# Clock.net
KiCad netlist of a schematic drawn in EAGLE
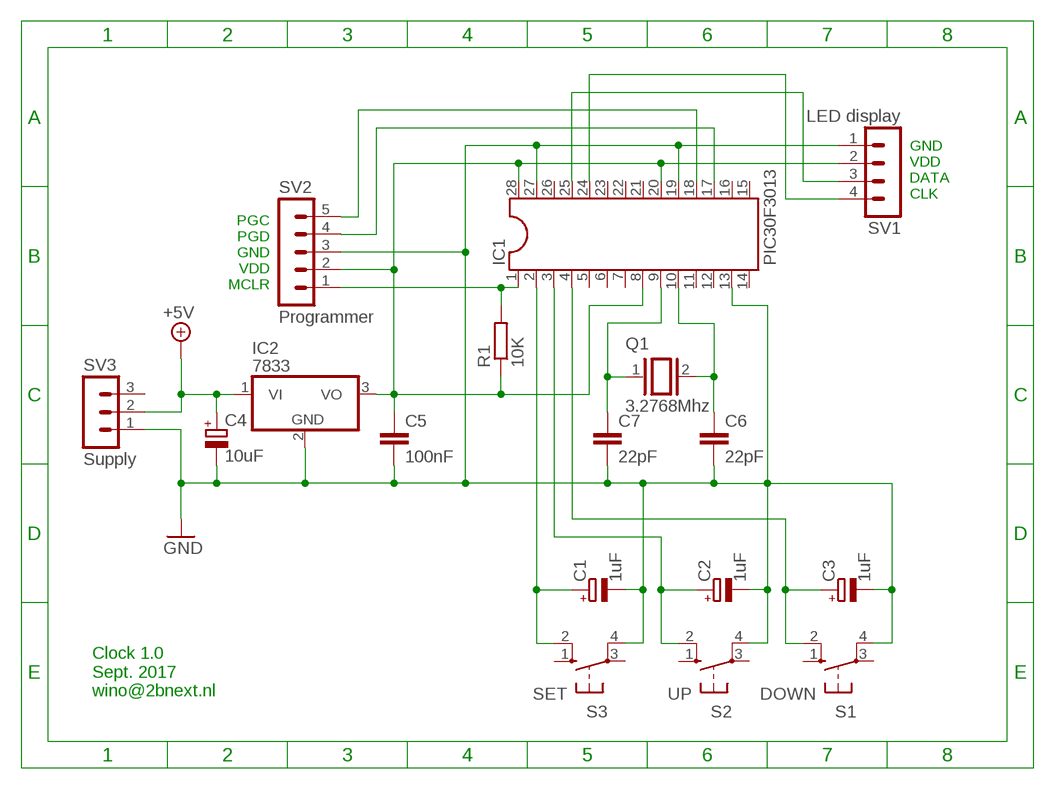
[diagram p0: schematic, sheet 1]

(export (version "E")
  (design (tool "Eeschema 10.0.6"))
  (components
    (comp (ref "C1")
      (value "1uF")
      (footprint "eagle-import:E2,5-5")
      (libsource (lib "eagle-import") (part "CPOL-EUE2.5-5"))
    )
    (comp (ref "C2")
      (value "1uF")
      (footprint "eagle-import:E2,5-5")
      (libsource (lib "eagle-import") (part "CPOL-EUE2.5-5"))
    )
    (comp (ref "C3")
      (value "1uF")
      (footprint "eagle-import:E2,5-5")
      (libsource (lib "eagle-import") (part "CPOL-EUE2.5-5"))
    )
    (comp (ref "C4")
      (value "10uF")
      (footprint "eagle-import:E2,5-5")
      (libsource (lib "eagle-import") (part "CPOL-EUE2.5-5"))
    )
    (comp (ref "C5")
      (value "100nF")
      (footprint "eagle-import:C2.5-3")
      (libsource (lib "eagle-import") (part "C2,5-3"))
    )
    (comp (ref "C6")
      (value "22pF")
      (footprint "eagle-import:C2.5-3")
      (libsource (lib "eagle-import") (part "C2,5-3"))
    )
    (comp (ref "C7")
      (value "22pF")
      (footprint "eagle-import:C2.5-3")
      (libsource (lib "eagle-import") (part "C2,5-3"))
    )
    (comp (ref "IC1")
      (value "PIC30F3013")
      (footprint "eagle-import:DIL28-3")
      (libsource (lib "eagle-import") (part "DIL28-3"))
    )
    (comp (ref "IC2")
      (value "7833")
      (footprint "eagle-import:TO220H")
      (libsource (lib "eagle-import") (part "78T05"))
    )
    (comp (ref "Q1")
      (value "3.2768Mhz")
      (footprint "eagle-import:QS")
      (libsource (lib "eagle-import") (part "XTAL/S"))
    )
    (comp (ref "R1")
      (value "10K")
      (footprint "eagle-import:0207_7")
      (libsource (lib "eagle-import") (part "R-EU_0207/7"))
    )
    (comp (ref "S1")
      (value "DOWN")
      (footprint "eagle-import:B3F-10XX")
      (fields (field (name "MPN") "B3F-1000"))
      (libsource (lib "eagle-import") (part "10-XX"))
    )
    (comp (ref "S2")
      (value "UP")
      (footprint "eagle-import:B3F-10XX")
      (fields (field (name "MPN") "B3F-1000"))
      (libsource (lib "eagle-import") (part "10-XX"))
    )
    (comp (ref "S3")
      (value "SET")
      (footprint "eagle-import:B3F-10XX")
      (fields (field (name "MPN") "B3F-1000"))
      (libsource (lib "eagle-import") (part "10-XX"))
    )
    (comp (ref "SV1")
      (value "LED display")
      (footprint "eagle-import:MA04-1")
      (libsource (lib "eagle-import") (part "MA04-1"))
    )
    (comp (ref "SV2")
      (value "Programmer")
      (footprint "eagle-import:MA05-1")
      (libsource (lib "eagle-import") (part "MA05-1"))
    )
    (comp (ref "SV3")
      (value "Supply")
      (footprint "eagle-import:MA03-1")
      (libsource (lib "eagle-import") (part "MA03-1"))
    )
  )
  (nets
    (net (code "1") (name "+5V") (class "Default")
      (node (ref "C4") (pin "+") (pinfunction "+_+") (pintype "passive"))
      (node (ref "IC2") (pin "1") (pinfunction "VI_1") (pintype "input"))
      (node (ref "SV3") (pin "2") (pinfunction "2_2") (pintype "passive"))
    )
    (net (code "2") (name "GND") (class "Default")
      (node (ref "C1") (pin "-") (pinfunction "-_-") (pintype "passive"))
      (node (ref "C2") (pin "-") (pinfunction "-_-") (pintype "passive"))
      (node (ref "C3") (pin "-") (pinfunction "-_-") (pintype "passive"))
      (node (ref "C4") (pin "-") (pinfunction "-_-") (pintype "passive"))
      (node (ref "C5") (pin "2") (pinfunction "2_2") (pintype "passive"))
      (node (ref "C6") (pin "2") (pinfunction "2_2") (pintype "passive"))
      (node (ref "C7") (pin "2") (pinfunction "2_2") (pintype "passive"))
      (node (ref "IC1") (pin "13") (pinfunction "13_13") (pintype "passive"))
      (node (ref "IC1") (pin "19") (pinfunction "19_19") (pintype "passive"))
      (node (ref "IC1") (pin "27") (pinfunction "27_27") (pintype "passive"))
      (node (ref "IC2") (pin "2") (pinfunction "GND_2") (pintype "passive"))
      (node (ref "S1") (pin "4") (pinfunction "P1_4") (pintype "passive"))
      (node (ref "S2") (pin "4") (pinfunction "P1_4") (pintype "passive"))
      (node (ref "S3") (pin "4") (pinfunction "P1_4") (pintype "passive"))
      (node (ref "SV1") (pin "1") (pinfunction "1_1") (pintype "passive"))
      (node (ref "SV2") (pin "3") (pinfunction "3_3") (pintype "passive"))
      (node (ref "SV3") (pin "1") (pinfunction "1_1") (pintype "passive"))
    )
    (net (code "3") (name "Net-(C6-Pad1)") (class "Default")
      (node (ref "C6") (pin "1") (pinfunction "1_1") (pintype "passive"))
      (node (ref "IC1") (pin "10") (pinfunction "10_10") (pintype "passive"))
      (node (ref "Q1") (pin "2") (pinfunction "2_2") (pintype "passive"))
    )
    (net (code "4") (name "Net-(C7-Pad1)") (class "Default")
      (node (ref "C7") (pin "1") (pinfunction "1_1") (pintype "passive"))
      (node (ref "IC1") (pin "9") (pinfunction "9_9") (pintype "passive"))
      (node (ref "Q1") (pin "1") (pinfunction "1_1") (pintype "passive"))
    )
    (net (code "5") (name "Net-(IC1-Pad1)") (class "Default")
      (node (ref "IC1") (pin "1") (pinfunction "1_1") (pintype "passive"))
      (node (ref "R1") (pin "2") (pinfunction "2_2") (pintype "passive"))
      (node (ref "SV2") (pin "1") (pinfunction "1_1") (pintype "passive"))
    )
    (net (code "6") (name "Net-(IC1-Pad17)") (class "Default")
      (node (ref "IC1") (pin "17") (pinfunction "17_17") (pintype "passive"))
      (node (ref "SV2") (pin "4") (pinfunction "4_4") (pintype "passive"))
    )
    (net (code "7") (name "Net-(IC1-Pad18)") (class "Default")
      (node (ref "IC1") (pin "18") (pinfunction "18_18") (pintype "passive"))
      (node (ref "SV2") (pin "5") (pinfunction "5_5") (pintype "passive"))
    )
    (net (code "8") (name "Net-(IC1-Pad24)") (class "Default")
      (node (ref "IC1") (pin "24") (pinfunction "24_24") (pintype "passive"))
      (node (ref "SV1") (pin "4") (pinfunction "4_4") (pintype "passive"))
    )
    (net (code "9") (name "Net-(IC1-Pad25)") (class "Default")
      (node (ref "IC1") (pin "25") (pinfunction "25_25") (pintype "passive"))
      (node (ref "SV1") (pin "3") (pinfunction "3_3") (pintype "passive"))
    )
    (net (code "10") (name "Net-(IC2-VO)") (class "Default")
      (node (ref "C5") (pin "1") (pinfunction "1_1") (pintype "passive"))
      (node (ref "IC1") (pin "20") (pinfunction "20_20") (pintype "passive"))
      (node (ref "IC1") (pin "28") (pinfunction "28_28") (pintype "passive"))
      (node (ref "IC1") (pin "8") (pinfunction "8_8") (pintype "passive"))
      (node (ref "IC2") (pin "3") (pinfunction "VO_3") (pintype "passive"))
      (node (ref "R1") (pin "1") (pinfunction "1_1") (pintype "passive"))
      (node (ref "SV1") (pin "2") (pinfunction "2_2") (pintype "passive"))
      (node (ref "SV2") (pin "2") (pinfunction "2_2") (pintype "passive"))
    )
    (net (code "11") (name "Net-(S1-S1)") (class "Default")
      (node (ref "C3") (pin "+") (pinfunction "+_+") (pintype "passive"))
      (node (ref "IC1") (pin "4") (pinfunction "4_4") (pintype "passive"))
      (node (ref "S1") (pin "2") (pinfunction "S1_2") (pintype "passive"))
    )
    (net (code "12") (name "Net-(S2-S1)") (class "Default")
      (node (ref "C2") (pin "+") (pinfunction "+_+") (pintype "passive"))
      (node (ref "IC1") (pin "3") (pinfunction "3_3") (pintype "passive"))
      (node (ref "S2") (pin "2") (pinfunction "S1_2") (pintype "passive"))
    )
    (net (code "13") (name "Net-(S3-S1)") (class "Default")
      (node (ref "C1") (pin "+") (pinfunction "+_+") (pintype "passive"))
      (node (ref "IC1") (pin "2") (pinfunction "2_2") (pintype "passive"))
      (node (ref "S3") (pin "2") (pinfunction "S1_2") (pintype "passive"))
    )
    (net (code "14") (name "unconnected-(IC1-Pad5)") (class "Default")
      (node (ref "IC1") (pin "5") (pinfunction "5_5") (pintype "passive"))
    )
    (net (code "15") (name "unconnected-(IC1-Pad6)") (class "Default")
      (node (ref "IC1") (pin "6") (pinfunction "6_6") (pintype "passive"))
    )
    (net (code "16") (name "unconnected-(IC1-Pad7)") (class "Default")
      (node (ref "IC1") (pin "7") (pinfunction "7_7") (pintype "passive"))
    )
    (net (code "17") (name "unconnected-(IC1-Pad11)") (class "Default")
      (node (ref "IC1") (pin "11") (pinfunction "11_11") (pintype "passive"))
    )
    (net (code "18") (name "unconnected-(IC1-Pad12)") (class "Default")
      (node (ref "IC1") (pin "12") (pinfunction "12_12") (pintype "passive"))
    )
    (net (code "19") (name "unconnected-(IC1-Pad14)") (class "Default")
      (node (ref "IC1") (pin "14") (pinfunction "14_14") (pintype "passive"))
    )
    (net (code "20") (name "unconnected-(IC1-Pad15)") (class "Default")
      (node (ref "IC1") (pin "15") (pinfunction "15_15") (pintype "passive"))
    )
    (net (code "21") (name "unconnected-(IC1-Pad16)") (class "Default")
      (node (ref "IC1") (pin "16") (pinfunction "16_16") (pintype "passive"))
    )
    (net (code "22") (name "unconnected-(IC1-Pad21)") (class "Default")
      (node (ref "IC1") (pin "21") (pinfunction "21_21") (pintype "passive"))
    )
    (net (code "23") (name "unconnected-(IC1-Pad22)") (class "Default")
      (node (ref "IC1") (pin "22") (pinfunction "22_22") (pintype "passive"))
    )
    (net (code "24") (name "unconnected-(IC1-Pad23)") (class "Default")
      (node (ref "IC1") (pin "23") (pinfunction "23_23") (pintype "passive"))
    )
    (net (code "25") (name "unconnected-(IC1-Pad26)") (class "Default")
      (node (ref "IC1") (pin "26") (pinfunction "26_26") (pintype "passive"))
    )
    (net (code "26") (name "unconnected-(S1-P-Pad3)") (class "Default")
      (node (ref "S1") (pin "3") (pinfunction "P_3") (pintype "passive"))
    )
    (net (code "27") (name "unconnected-(S1-S-Pad1)") (class "Default")
      (node (ref "S1") (pin "1") (pinfunction "S_1") (pintype "passive"))
    )
    (net (code "28") (name "unconnected-(S2-P-Pad3)") (class "Default")
      (node (ref "S2") (pin "3") (pinfunction "P_3") (pintype "passive"))
    )
    (net (code "29") (name "unconnected-(S2-S-Pad1)") (class "Default")
      (node (ref "S2") (pin "1") (pinfunction "S_1") (pintype "passive"))
    )
    (net (code "30") (name "unconnected-(S3-P-Pad3)") (class "Default")
      (node (ref "S3") (pin "3") (pinfunction "P_3") (pintype "passive"))
    )
    (net (code "31") (name "unconnected-(S3-S-Pad1)") (class "Default")
      (node (ref "S3") (pin "1") (pinfunction "S_1") (pintype "passive"))
    )
    (net (code "32") (name "unconnected-(SV3-Pad3)") (class "Default")
      (node (ref "SV3") (pin "3") (pinfunction "3_3") (pintype "passive"))
    )
  )
)
